# LVDS.net
KiCad netlist of a schematic drawn in Altium Designer
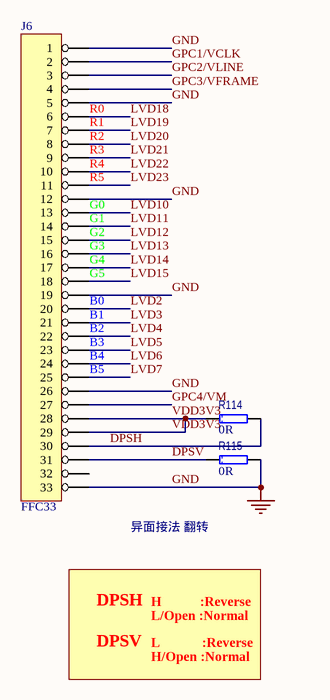
[diagram p0: LVDS.SchDoc]

(export (version "E")
  (design (tool "Eeschema 10.0.6"))
  (components
    (comp (ref "J6")
      (value "FFC33")
      (footprint "FFC/SM0.5-2H33")
      (description "CON")
      (libsource (lib "*") (part "HEADER 33"))
    )
    (comp (ref "R114")
      (value "0R")
      (footprint "1608[0603]R")
      (description "RES")
      (fields (field (name "MANUFACTURER") "vishay"))
      (libsource (lib "*") (part "RES"))
    )
    (comp (ref "R115")
      (value "0R")
      (footprint "1608[0603]R")
      (description "RES")
      (fields (field (name "MANUFACTURER") "vishay"))
      (libsource (lib "*") (part "RES"))
    )
  )
  (nets
    (net (code "2") (name "/DPSH") (class "Default")
      (node (ref "J6") (pin "30") (pinfunction "30_30") (pintype "passive"))
      (node (ref "R114") (pin "2") (pinfunction "2_2") (pintype "passive"))
    )
    (net (code "3") (name "/DPSV") (class "Default")
      (node (ref "J6") (pin "31") (pinfunction "31_31") (pintype "passive"))
      (node (ref "R115") (pin "1") (pinfunction "1_1") (pintype "passive"))
    )
    (net (code "4") (name "/GPC1{slash}VCLK") (class "Default")
      (node (ref "J6") (pin "2") (pinfunction "2_2") (pintype "passive"))
    )
    (net (code "5") (name "/GPC2{slash}VLINE") (class "Default")
      (node (ref "J6") (pin "3") (pinfunction "3_3") (pintype "passive"))
    )
    (net (code "6") (name "/GPC3{slash}VFRAME") (class "Default")
      (node (ref "J6") (pin "4") (pinfunction "4_4") (pintype "passive"))
    )
    (net (code "7") (name "/GPC4{slash}VM") (class "Default")
      (node (ref "J6") (pin "27") (pinfunction "27_27") (pintype "passive"))
    )
    (net (code "8") (name "/LVD2") (class "Default")
      (node (ref "J6") (pin "20") (pinfunction "20_20") (pintype "passive"))
    )
    (net (code "9") (name "/LVD3") (class "Default")
      (node (ref "J6") (pin "21") (pinfunction "21_21") (pintype "passive"))
    )
    (net (code "10") (name "/LVD4") (class "Default")
      (node (ref "J6") (pin "22") (pinfunction "22_22") (pintype "passive"))
    )
    (net (code "11") (name "/LVD5") (class "Default")
      (node (ref "J6") (pin "23") (pinfunction "23_23") (pintype "passive"))
    )
    (net (code "12") (name "/LVD6") (class "Default")
      (node (ref "J6") (pin "24") (pinfunction "24_24") (pintype "passive"))
    )
    (net (code "13") (name "/LVD7") (class "Default")
      (node (ref "J6") (pin "25") (pinfunction "25_25") (pintype "passive"))
    )
    (net (code "14") (name "/LVD10") (class "Default")
      (node (ref "J6") (pin "13") (pinfunction "13_13") (pintype "passive"))
    )
    (net (code "15") (name "/LVD11") (class "Default")
      (node (ref "J6") (pin "14") (pinfunction "14_14") (pintype "passive"))
    )
    (net (code "16") (name "/LVD12") (class "Default")
      (node (ref "J6") (pin "15") (pinfunction "15_15") (pintype "passive"))
    )
    (net (code "17") (name "/LVD13") (class "Default")
      (node (ref "J6") (pin "16") (pinfunction "16_16") (pintype "passive"))
    )
    (net (code "18") (name "/LVD14") (class "Default")
      (node (ref "J6") (pin "17") (pinfunction "17_17") (pintype "passive"))
    )
    (net (code "19") (name "/LVD15") (class "Default")
      (node (ref "J6") (pin "18") (pinfunction "18_18") (pintype "passive"))
    )
    (net (code "20") (name "/LVD18") (class "Default")
      (node (ref "J6") (pin "6") (pinfunction "6_6") (pintype "passive"))
    )
    (net (code "21") (name "/LVD19") (class "Default")
      (node (ref "J6") (pin "7") (pinfunction "7_7") (pintype "passive"))
    )
    (net (code "22") (name "/LVD20") (class "Default")
      (node (ref "J6") (pin "8") (pinfunction "8_8") (pintype "passive"))
    )
    (net (code "23") (name "/LVD21") (class "Default")
      (node (ref "J6") (pin "9") (pinfunction "9_9") (pintype "passive"))
    )
    (net (code "24") (name "/LVD22") (class "Default")
      (node (ref "J6") (pin "10") (pinfunction "10_10") (pintype "passive"))
    )
    (net (code "25") (name "/LVD23") (class "Default")
      (node (ref "J6") (pin "11") (pinfunction "11_11") (pintype "passive"))
    )
    (net (code "26") (name "/VDD3V3") (class "Default")
      (node (ref "J6") (pin "28") (pinfunction "28_28") (pintype "passive"))
      (node (ref "J6") (pin "29") (pinfunction "29_29") (pintype "passive"))
      (node (ref "R114") (pin "1") (pinfunction "1_1") (pintype "passive"))
    )
    (net (code "27") (name "GND") (class "Default")
      (node (ref "J6") (pin "1") (pinfunction "1_1") (pintype "passive"))
      (node (ref "J6") (pin "12") (pinfunction "12_12") (pintype "passive"))
      (node (ref "J6") (pin "19") (pinfunction "19_19") (pintype "passive"))
      (node (ref "J6") (pin "26") (pinfunction "26_26") (pintype "passive"))
      (node (ref "J6") (pin "33") (pinfunction "33_33") (pintype "passive"))
      (node (ref "J6") (pin "5") (pinfunction "5_5") (pintype "passive"))
      (node (ref "R115") (pin "2") (pinfunction "2_2") (pintype "passive"))
    )
    (net (code "28") (name "unconnected-(J6-Pad32)") (class "Default")
      (node (ref "J6") (pin "32") (pinfunction "32_32") (pintype "passive"))
    )
  )
)
